# red-cluster.net
KiCad netlist of a schematic drawn in EAGLE
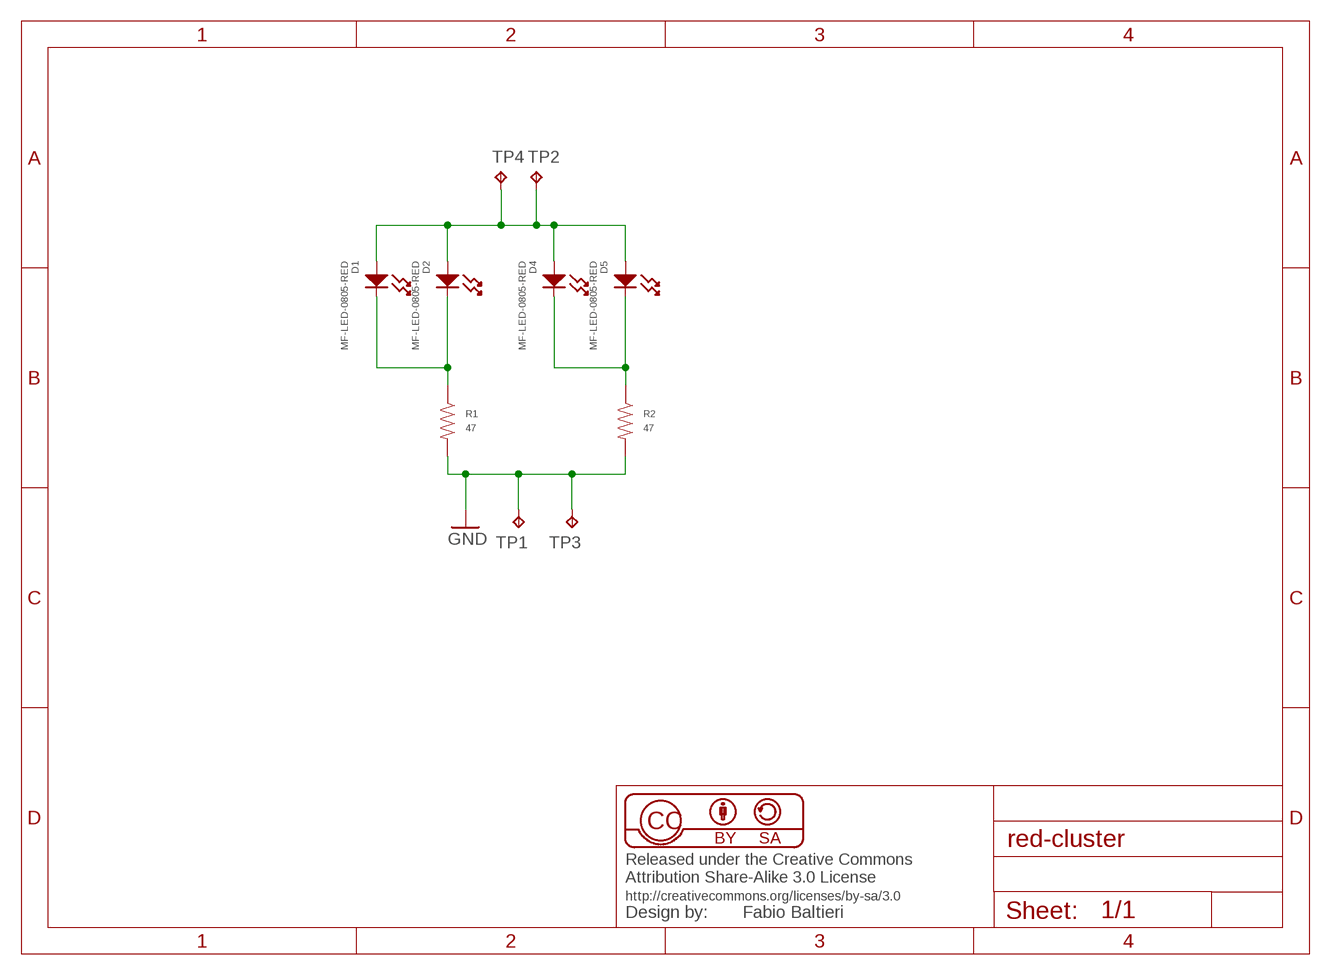
[diagram p0: schematic, sheet 1]

(export (version "E")
  (design (tool "Eeschema 10.0.6"))
  (components
    (comp (ref "D1")
      (value "MF-LED-0805-RED")
      (footprint "eagle-import:LED0805")
      (fields (field (name "HOUSEPART") "YES"))
      (libsource (lib "eagle-import") (part "LED_SINGLE-0805-RED"))
    )
    (comp (ref "D2")
      (value "MF-LED-0805-RED")
      (footprint "eagle-import:LED0805")
      (fields (field (name "HOUSEPART") "YES"))
      (libsource (lib "eagle-import") (part "LED_SINGLE-0805-RED"))
    )
    (comp (ref "D4")
      (value "MF-LED-0805-RED")
      (footprint "eagle-import:LED0805")
      (fields (field (name "HOUSEPART") "YES"))
      (libsource (lib "eagle-import") (part "LED_SINGLE-0805-RED"))
    )
    (comp (ref "D5")
      (value "MF-LED-0805-RED")
      (footprint "eagle-import:LED0805")
      (fields (field (name "HOUSEPART") "YES"))
      (libsource (lib "eagle-import") (part "LED_SINGLE-0805-RED"))
    )
    (comp (ref "R1")
      (value "47")
      (footprint "eagle-import:R0805")
      (libsource (lib "eagle-import") (part "RESISTOR_0805"))
    )
    (comp (ref "R2")
      (value "47")
      (footprint "eagle-import:R0805")
      (libsource (lib "eagle-import") (part "RESISTOR_0805"))
    )
    (comp (ref "TP1")
      (value "TPTP15R")
      (footprint "eagle-import:TP15R")
      (libsource (lib "eagle-import") (part "TPTP15R"))
    )
    (comp (ref "TP2")
      (value "TPTP15R")
      (footprint "eagle-import:TP15R")
      (libsource (lib "eagle-import") (part "TPTP15R"))
    )
    (comp (ref "TP3")
      (value "TPTP15R")
      (footprint "eagle-import:TP15R")
      (libsource (lib "eagle-import") (part "TPTP15R"))
    )
    (comp (ref "TP4")
      (value "TPTP15R")
      (footprint "eagle-import:TP15R")
      (libsource (lib "eagle-import") (part "TPTP15R"))
    )
  )
  (nets
    (net (code "1") (name "GND") (class "Default")
      (node (ref "R1") (pin "P$2") (pinfunction "P$2_P$2") (pintype "passive"))
      (node (ref "R2") (pin "P$2") (pinfunction "P$2_P$2") (pintype "passive"))
      (node (ref "TP1") (pin "TP") (pinfunction "TP_TP") (pintype "input"))
      (node (ref "TP3") (pin "TP") (pinfunction "TP_TP") (pintype "input"))
    )
    (net (code "2") (name "Net-(D1-PadANODE)") (class "Default")
      (node (ref "D1") (pin "ANODE") (pinfunction "ANODE_ANODE") (pintype "power_in"))
      (node (ref "D2") (pin "ANODE") (pinfunction "ANODE_ANODE") (pintype "power_in"))
      (node (ref "D4") (pin "ANODE") (pinfunction "ANODE_ANODE") (pintype "power_in"))
      (node (ref "D5") (pin "ANODE") (pinfunction "ANODE_ANODE") (pintype "power_in"))
      (node (ref "TP2") (pin "TP") (pinfunction "TP_TP") (pintype "input"))
      (node (ref "TP4") (pin "TP") (pinfunction "TP_TP") (pintype "input"))
    )
    (net (code "3") (name "Net-(D1-PadCATHODE)") (class "Default")
      (node (ref "D1") (pin "CATHODE") (pinfunction "CATHODE_CATHODE") (pintype "power_in"))
      (node (ref "D2") (pin "CATHODE") (pinfunction "CATHODE_CATHODE") (pintype "power_in"))
      (node (ref "R1") (pin "P$1") (pinfunction "P$1_P$1") (pintype "passive"))
    )
    (net (code "4") (name "Net-(D4-PadCATHODE)") (class "Default")
      (node (ref "D4") (pin "CATHODE") (pinfunction "CATHODE_CATHODE") (pintype "power_in"))
      (node (ref "D5") (pin "CATHODE") (pinfunction "CATHODE_CATHODE") (pintype "power_in"))
      (node (ref "R2") (pin "P$1") (pinfunction "P$1_P$1") (pintype "passive"))
    )
  )
)
